# watering.net
KiCad netlist of a schematic drawn in EAGLE
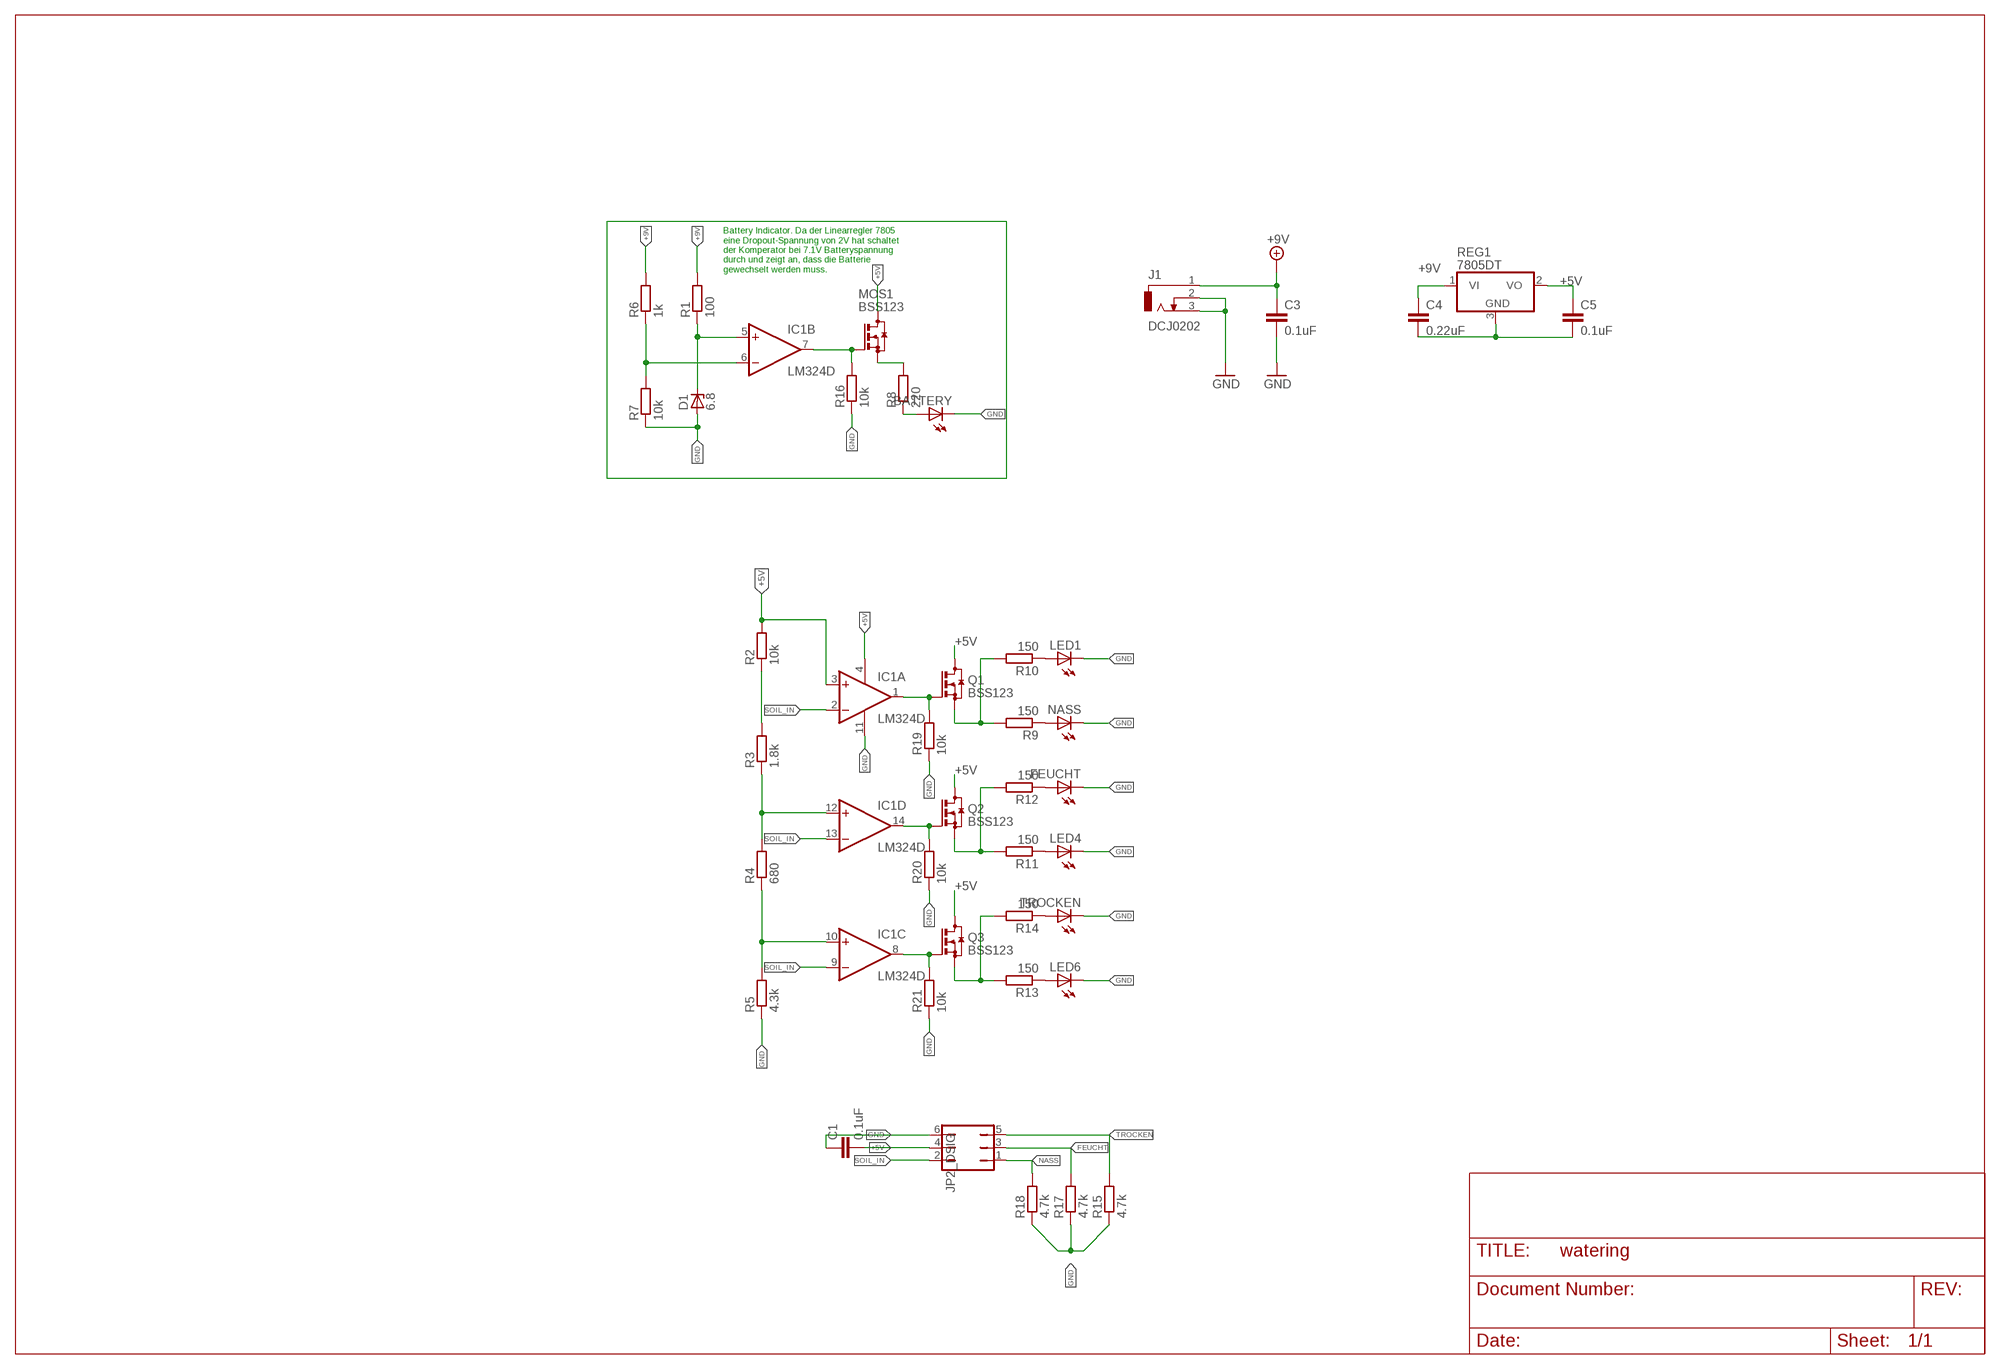
[diagram p0: schematic, sheet 1]

(export (version "E")
  (design (tool "Eeschema 10.0.6"))
  (components
    (comp (ref "BATTERY")
      (value "LEDSML0805")
      (footprint "eagle-import:SML0805")
      (libsource (lib "eagle-import") (part "LEDSML0805"))
    )
    (comp (ref "C1")
      (value "0.1uF")
      (footprint "eagle-import:C0805")
      (libsource (lib "eagle-import") (part "C-EUC0805"))
    )
    (comp (ref "C3")
      (value "0.1uF")
      (footprint "eagle-import:C0805")
      (libsource (lib "eagle-import") (part "C-EUC0805"))
    )
    (comp (ref "C4")
      (value "0.22uF")
      (footprint "eagle-import:C0805")
      (libsource (lib "eagle-import") (part "C-EUC0805"))
    )
    (comp (ref "C5")
      (value "0.1uF")
      (footprint "eagle-import:C0805")
      (libsource (lib "eagle-import") (part "C-EUC0805"))
    )
    (comp (ref "D1")
      (value "6.8")
      (footprint "eagle-import:SMB")
      (libsource (lib "eagle-import") (part "ZENER-DIODESMB"))
    )
    (comp (ref "FEUCHT")
      (value "LEDSML0805")
      (footprint "eagle-import:SML0805")
      (libsource (lib "eagle-import") (part "LEDSML0805"))
    )
    (comp (ref "IC1")
      (value "LM324D")
      (footprint "eagle-import:SO14")
      (libsource (lib "eagle-import") (part "LM324D"))
    )
    (comp (ref "J1")
      (value "DCJ0202")
      (footprint "eagle-import:DCJ0202")
      (libsource (lib "eagle-import") (part "DCJ0202"))
    )
    (comp (ref "JP1")
      (value "JP2_DSIG")
      (footprint "eagle-import:JP3Q")
      (libsource (lib "eagle-import") (part "JP3Q"))
    )
    (comp (ref "LED1")
      (value "LEDSML0805")
      (footprint "eagle-import:SML0805")
      (libsource (lib "eagle-import") (part "LEDSML0805"))
    )
    (comp (ref "LED4")
      (value "LEDSML0805")
      (footprint "eagle-import:SML0805")
      (libsource (lib "eagle-import") (part "LEDSML0805"))
    )
    (comp (ref "LED6")
      (value "LEDSML0805")
      (footprint "eagle-import:SML0805")
      (libsource (lib "eagle-import") (part "LEDSML0805"))
    )
    (comp (ref "MOS1")
      (value "BSS123")
      (footprint "eagle-import:SOT23")
      (libsource (lib "eagle-import") (part "BSS123"))
    )
    (comp (ref "NASS")
      (value "LEDSML0805")
      (footprint "eagle-import:SML0805")
      (libsource (lib "eagle-import") (part "LEDSML0805"))
    )
    (comp (ref "Q1")
      (value "BSS123")
      (footprint "eagle-import:SOT23")
      (libsource (lib "eagle-import") (part "transistor-small-signal_401_BSS123"))
    )
    (comp (ref "Q2")
      (value "BSS123")
      (footprint "eagle-import:SOT23")
      (libsource (lib "eagle-import") (part "transistor-small-signal_401_BSS123"))
    )
    (comp (ref "Q3")
      (value "BSS123")
      (footprint "eagle-import:SOT23")
      (libsource (lib "eagle-import") (part "transistor-small-signal_401_BSS123"))
    )
    (comp (ref "R1")
      (value "100")
      (footprint "eagle-import:M0805")
      (libsource (lib "eagle-import") (part "R-EU_M0805"))
    )
    (comp (ref "R2")
      (value "10k")
      (footprint "eagle-import:M0805")
      (libsource (lib "eagle-import") (part "R-EU_M0805"))
    )
    (comp (ref "R3")
      (value "1.8k")
      (footprint "eagle-import:M0805")
      (libsource (lib "eagle-import") (part "R-EU_M0805"))
    )
    (comp (ref "R4")
      (value "680")
      (footprint "eagle-import:M0805")
      (libsource (lib "eagle-import") (part "R-EU_M0805"))
    )
    (comp (ref "R5")
      (value "4.3k")
      (footprint "eagle-import:M0805")
      (libsource (lib "eagle-import") (part "R-EU_M0805"))
    )
    (comp (ref "R6")
      (value "1k")
      (footprint "eagle-import:M0805")
      (libsource (lib "eagle-import") (part "R-EU_M0805"))
    )
    (comp (ref "R7")
      (value "10k")
      (footprint "eagle-import:M0805")
      (libsource (lib "eagle-import") (part "R-EU_M0805"))
    )
    (comp (ref "R8")
      (value "220")
      (footprint "eagle-import:M0805")
      (libsource (lib "eagle-import") (part "R-EU_M0805"))
    )
    (comp (ref "R9")
      (value "150")
      (footprint "eagle-import:M0805")
      (libsource (lib "eagle-import") (part "R-EU_M0805"))
    )
    (comp (ref "R10")
      (value "150")
      (footprint "eagle-import:M0805")
      (libsource (lib "eagle-import") (part "R-EU_M0805"))
    )
    (comp (ref "R11")
      (value "150")
      (footprint "eagle-import:M0805")
      (libsource (lib "eagle-import") (part "R-EU_M0805"))
    )
    (comp (ref "R12")
      (value "150")
      (footprint "eagle-import:M0805")
      (libsource (lib "eagle-import") (part "R-EU_M0805"))
    )
    (comp (ref "R13")
      (value "150")
      (footprint "eagle-import:M0805")
      (libsource (lib "eagle-import") (part "R-EU_M0805"))
    )
    (comp (ref "R14")
      (value "150")
      (footprint "eagle-import:M0805")
      (libsource (lib "eagle-import") (part "R-EU_M0805"))
    )
    (comp (ref "R15")
      (value "4.7k")
      (footprint "eagle-import:M0805")
      (libsource (lib "eagle-import") (part "R-EU_M0805"))
    )
    (comp (ref "R16")
      (value "10k")
      (footprint "eagle-import:M0805")
      (libsource (lib "eagle-import") (part "R-EU_M0805"))
    )
    (comp (ref "R17")
      (value "4.7k")
      (footprint "eagle-import:M0805")
      (libsource (lib "eagle-import") (part "R-EU_M0805"))
    )
    (comp (ref "R18")
      (value "4.7k")
      (footprint "eagle-import:M0805")
      (libsource (lib "eagle-import") (part "R-EU_M0805"))
    )
    (comp (ref "R19")
      (value "10k")
      (footprint "eagle-import:M0805")
      (libsource (lib "eagle-import") (part "R-EU_M0805"))
    )
    (comp (ref "R20")
      (value "10k")
      (footprint "eagle-import:M0805")
      (libsource (lib "eagle-import") (part "R-EU_M0805"))
    )
    (comp (ref "R21")
      (value "10k")
      (footprint "eagle-import:M0805")
      (libsource (lib "eagle-import") (part "R-EU_M0805"))
    )
    (comp (ref "REG1")
      (value "7805DT")
      (footprint "eagle-import:TO252")
      (libsource (lib "eagle-import") (part "78DT05"))
    )
    (comp (ref "TROCKEN")
      (value "LEDSML0805")
      (footprint "eagle-import:SML0805")
      (libsource (lib "eagle-import") (part "LEDSML0805"))
    )
  )
  (nets
    (net (code "1") (name "+5V") (class "Default")
      (node (ref "C1") (pin "2") (pinfunction "2_2") (pintype "passive"))
      (node (ref "C5") (pin "1") (pinfunction "1_1") (pintype "passive"))
      (node (ref "IC1") (pin "3") (pinfunction "+IN_3") (pintype "input"))
      (node (ref "IC1") (pin "4") (pinfunction "V+_4") (pintype "power_in"))
      (node (ref "JP1") (pin "4") (pinfunction "4_4") (pintype "passive"))
      (node (ref "MOS1") (pin "3") (pinfunction "D_3") (pintype "passive"))
      (node (ref "Q1") (pin "3") (pinfunction "D_3") (pintype "passive"))
      (node (ref "Q2") (pin "3") (pinfunction "D_3") (pintype "passive"))
      (node (ref "Q3") (pin "3") (pinfunction "D_3") (pintype "passive"))
      (node (ref "R2") (pin "2") (pinfunction "2_2") (pintype "passive"))
      (node (ref "REG1") (pin "2") (pinfunction "VO_2") (pintype "passive"))
    )
    (net (code "2") (name "+9V") (class "Default")
      (node (ref "C3") (pin "1") (pinfunction "1_1") (pintype "passive"))
      (node (ref "C4") (pin "1") (pinfunction "1_1") (pintype "passive"))
      (node (ref "J1") (pin "1") (pinfunction "1_1") (pintype "passive"))
      (node (ref "R1") (pin "2") (pinfunction "2_2") (pintype "passive"))
      (node (ref "R6") (pin "2") (pinfunction "2_2") (pintype "passive"))
      (node (ref "REG1") (pin "1") (pinfunction "VI_1") (pintype "input"))
    )
    (net (code "3") (name "FEUCHT") (class "Default")
      (node (ref "JP1") (pin "3") (pinfunction "3_3") (pintype "passive"))
      (node (ref "Q2") (pin "2") (pinfunction "S_2") (pintype "passive"))
      (node (ref "R11") (pin "2") (pinfunction "2_2") (pintype "passive"))
      (node (ref "R12") (pin "2") (pinfunction "2_2") (pintype "passive"))
      (node (ref "R17") (pin "2") (pinfunction "2_2") (pintype "passive"))
    )
    (net (code "4") (name "GND") (class "Default")
      (node (ref "BATTERY") (pin "C") (pinfunction "C_C") (pintype "passive"))
      (node (ref "C1") (pin "1") (pinfunction "1_1") (pintype "passive"))
      (node (ref "C3") (pin "2") (pinfunction "2_2") (pintype "passive"))
      (node (ref "C4") (pin "2") (pinfunction "2_2") (pintype "passive"))
      (node (ref "C5") (pin "2") (pinfunction "2_2") (pintype "passive"))
      (node (ref "D1") (pin "A") (pinfunction "A_A") (pintype "passive"))
      (node (ref "FEUCHT") (pin "C") (pinfunction "C_C") (pintype "passive"))
      (node (ref "IC1") (pin "11") (pinfunction "V-_11") (pintype "power_in"))
      (node (ref "J1") (pin "2") (pinfunction "2_2") (pintype "passive"))
      (node (ref "J1") (pin "3") (pinfunction "3_3") (pintype "passive"))
      (node (ref "JP1") (pin "6") (pinfunction "6_6") (pintype "passive"))
      (node (ref "LED1") (pin "C") (pinfunction "C_C") (pintype "passive"))
      (node (ref "LED4") (pin "C") (pinfunction "C_C") (pintype "passive"))
      (node (ref "LED6") (pin "C") (pinfunction "C_C") (pintype "passive"))
      (node (ref "NASS") (pin "C") (pinfunction "C_C") (pintype "passive"))
      (node (ref "R15") (pin "1") (pinfunction "1_1") (pintype "passive"))
      (node (ref "R16") (pin "1") (pinfunction "1_1") (pintype "passive"))
      (node (ref "R17") (pin "1") (pinfunction "1_1") (pintype "passive"))
      (node (ref "R18") (pin "1") (pinfunction "1_1") (pintype "passive"))
      (node (ref "R19") (pin "1") (pinfunction "1_1") (pintype "passive"))
      (node (ref "R20") (pin "1") (pinfunction "1_1") (pintype "passive"))
      (node (ref "R21") (pin "1") (pinfunction "1_1") (pintype "passive"))
      (node (ref "R5") (pin "1") (pinfunction "1_1") (pintype "passive"))
      (node (ref "R7") (pin "1") (pinfunction "1_1") (pintype "passive"))
      (node (ref "REG1") (pin "3") (pinfunction "GND_3") (pintype "passive"))
      (node (ref "TROCKEN") (pin "C") (pinfunction "C_C") (pintype "passive"))
    )
    (net (code "5") (name "NASS") (class "Default")
      (node (ref "JP1") (pin "1") (pinfunction "1_1") (pintype "passive"))
      (node (ref "Q1") (pin "2") (pinfunction "S_2") (pintype "passive"))
      (node (ref "R10") (pin "2") (pinfunction "2_2") (pintype "passive"))
      (node (ref "R18") (pin "2") (pinfunction "2_2") (pintype "passive"))
      (node (ref "R9") (pin "2") (pinfunction "2_2") (pintype "passive"))
    )
    (net (code "6") (name "Net-(BATTERY-PadA)") (class "Default")
      (node (ref "BATTERY") (pin "A") (pinfunction "A_A") (pintype "passive"))
      (node (ref "R8") (pin "1") (pinfunction "1_1") (pintype "passive"))
    )
    (net (code "7") (name "Net-(FEUCHT-PadA)") (class "Default")
      (node (ref "FEUCHT") (pin "A") (pinfunction "A_A") (pintype "passive"))
      (node (ref "R12") (pin "1") (pinfunction "1_1") (pintype "passive"))
    )
    (net (code "8") (name "Net-(IC1A-OUT)") (class "Default")
      (node (ref "IC1") (pin "1") (pinfunction "OUT_1") (pintype "output"))
      (node (ref "Q1") (pin "1") (pinfunction "G_1") (pintype "passive"))
      (node (ref "R19") (pin "2") (pinfunction "2_2") (pintype "passive"))
    )
    (net (code "9") (name "Net-(IC1B-+IN)") (class "Default")
      (node (ref "D1") (pin "C") (pinfunction "C_C") (pintype "passive"))
      (node (ref "IC1") (pin "5") (pinfunction "+IN_5") (pintype "input"))
      (node (ref "R1") (pin "1") (pinfunction "1_1") (pintype "passive"))
    )
    (net (code "10") (name "Net-(IC1B--IN)") (class "Default")
      (node (ref "IC1") (pin "6") (pinfunction "-IN_6") (pintype "input"))
      (node (ref "R6") (pin "1") (pinfunction "1_1") (pintype "passive"))
      (node (ref "R7") (pin "2") (pinfunction "2_2") (pintype "passive"))
    )
    (net (code "11") (name "Net-(IC1B-OUT)") (class "Default")
      (node (ref "IC1") (pin "7") (pinfunction "OUT_7") (pintype "output"))
      (node (ref "MOS1") (pin "1") (pinfunction "G_1") (pintype "passive"))
      (node (ref "R16") (pin "2") (pinfunction "2_2") (pintype "passive"))
    )
    (net (code "12") (name "Net-(IC1C-+IN)") (class "Default")
      (node (ref "IC1") (pin "10") (pinfunction "+IN_10") (pintype "input"))
      (node (ref "R4") (pin "1") (pinfunction "1_1") (pintype "passive"))
      (node (ref "R5") (pin "2") (pinfunction "2_2") (pintype "passive"))
    )
    (net (code "13") (name "Net-(IC1C-OUT)") (class "Default")
      (node (ref "IC1") (pin "8") (pinfunction "OUT_8") (pintype "output"))
      (node (ref "Q3") (pin "1") (pinfunction "G_1") (pintype "passive"))
      (node (ref "R21") (pin "2") (pinfunction "2_2") (pintype "passive"))
    )
    (net (code "14") (name "Net-(IC1D-+IN)") (class "Default")
      (node (ref "IC1") (pin "12") (pinfunction "+IN_12") (pintype "input"))
      (node (ref "R3") (pin "1") (pinfunction "1_1") (pintype "passive"))
      (node (ref "R4") (pin "2") (pinfunction "2_2") (pintype "passive"))
    )
    (net (code "15") (name "Net-(IC1D-OUT)") (class "Default")
      (node (ref "IC1") (pin "14") (pinfunction "OUT_14") (pintype "output"))
      (node (ref "Q2") (pin "1") (pinfunction "G_1") (pintype "passive"))
      (node (ref "R20") (pin "2") (pinfunction "2_2") (pintype "passive"))
    )
    (net (code "16") (name "Net-(LED1-PadA)") (class "Default")
      (node (ref "LED1") (pin "A") (pinfunction "A_A") (pintype "passive"))
      (node (ref "R10") (pin "1") (pinfunction "1_1") (pintype "passive"))
    )
    (net (code "17") (name "Net-(LED4-PadA)") (class "Default")
      (node (ref "LED4") (pin "A") (pinfunction "A_A") (pintype "passive"))
      (node (ref "R11") (pin "1") (pinfunction "1_1") (pintype "passive"))
    )
    (net (code "18") (name "Net-(LED6-PadA)") (class "Default")
      (node (ref "LED6") (pin "A") (pinfunction "A_A") (pintype "passive"))
      (node (ref "R13") (pin "1") (pinfunction "1_1") (pintype "passive"))
    )
    (net (code "19") (name "Net-(MOS1-S)") (class "Default")
      (node (ref "MOS1") (pin "2") (pinfunction "S_2") (pintype "passive"))
      (node (ref "R8") (pin "2") (pinfunction "2_2") (pintype "passive"))
    )
    (net (code "20") (name "Net-(NASS-PadA)") (class "Default")
      (node (ref "NASS") (pin "A") (pinfunction "A_A") (pintype "passive"))
      (node (ref "R9") (pin "1") (pinfunction "1_1") (pintype "passive"))
    )
    (net (code "21") (name "Net-(R2-Pad1)") (class "Default")
      (node (ref "R2") (pin "1") (pinfunction "1_1") (pintype "passive"))
      (node (ref "R3") (pin "2") (pinfunction "2_2") (pintype "passive"))
    )
    (net (code "22") (name "Net-(R14-Pad1)") (class "Default")
      (node (ref "R14") (pin "1") (pinfunction "1_1") (pintype "passive"))
      (node (ref "TROCKEN") (pin "A") (pinfunction "A_A") (pintype "passive"))
    )
    (net (code "23") (name "SOIL_IN") (class "Default")
      (node (ref "IC1") (pin "13") (pinfunction "-IN_13") (pintype "input"))
      (node (ref "IC1") (pin "2") (pinfunction "-IN_2") (pintype "input"))
      (node (ref "IC1") (pin "9") (pinfunction "-IN_9") (pintype "input"))
      (node (ref "JP1") (pin "2") (pinfunction "2_2") (pintype "passive"))
    )
    (net (code "24") (name "TROCKEN") (class "Default")
      (node (ref "JP1") (pin "5") (pinfunction "5_5") (pintype "passive"))
      (node (ref "Q3") (pin "2") (pinfunction "S_2") (pintype "passive"))
      (node (ref "R13") (pin "2") (pinfunction "2_2") (pintype "passive"))
      (node (ref "R14") (pin "2") (pinfunction "2_2") (pintype "passive"))
      (node (ref "R15") (pin "2") (pinfunction "2_2") (pintype "passive"))
    )
  )
)
